# akcelerometr.net
KiCad netlist of a schematic drawn in Altium Designer
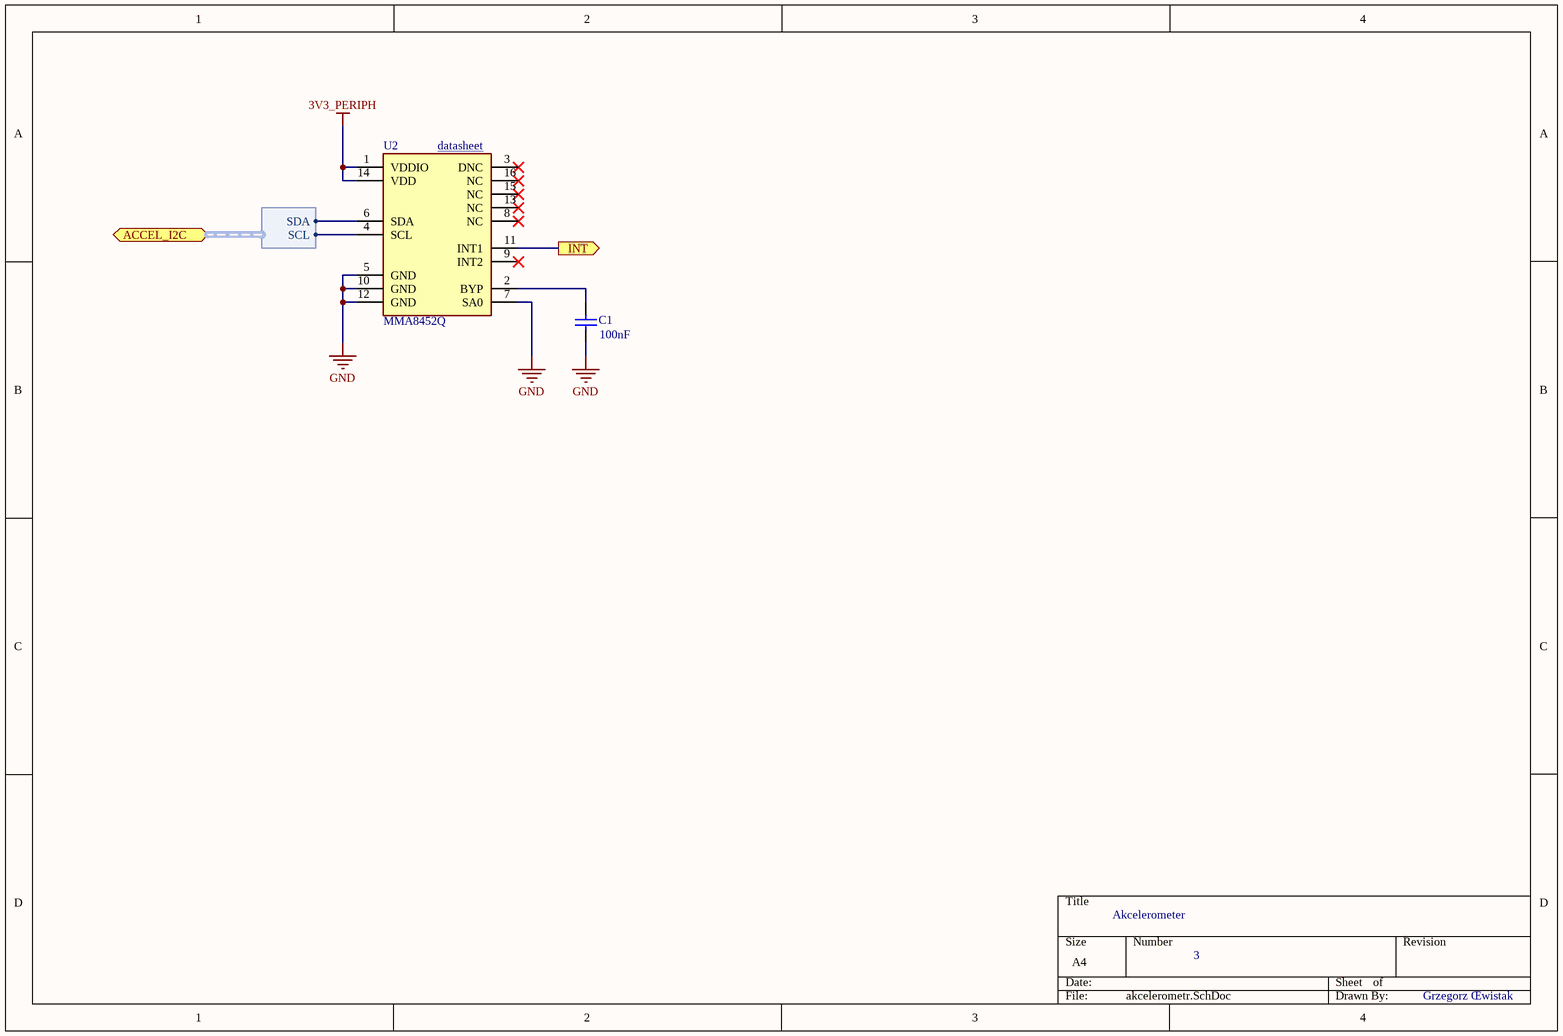
[diagram p0: akcelerometr.SchDoc]

(export (version "E")
  (design (tool "Eeschema 10.0.6"))
  (components
    (comp (ref "C1")
      (value "100nF")
      (footprint "C0805")
      (description "Capacitor")
      (fields (field (name "Comment") "Cap") (field (name "PUBLISHER") "Altium Limited"))
      (libsource (lib "Miscellaneous Devices") (part "Cap"))
    )
    (comp (ref "U2")
      (value "MMA8452Q")
      (footprint "QFN-16")
      (description "Accelerometer")
      (fields
        (field (name "MANUFACTURER_PART_NUMBER") "MMA8452QR1")
        (field (name "MOUSER PART NUMBER") "841-MMA8452QR1")
      )
      (libsource (lib "lib") (part "MMA8452QR1"))
    )
  )
  (nets
    (net (code "2") (name "/INT") (class "Default")
      (node (ref "U2") (pin "11") (pinfunction "INT1_11") (pintype "passive"))
    )
    (net (code "3") (name "/SCL") (class "Default")
      (node (ref "U2") (pin "4") (pinfunction "SCL_4") (pintype "passive"))
    )
    (net (code "4") (name "/SDA") (class "Default")
      (node (ref "U2") (pin "6") (pinfunction "SDA_6") (pintype "passive"))
    )
    (net (code "6") (name "3V3_PERIPH") (class "Default")
      (node (ref "U2") (pin "1") (pinfunction "VDDIO_1") (pintype "passive"))
      (node (ref "U2") (pin "14") (pinfunction "VDD_14") (pintype "passive"))
    )
    (net (code "7") (name "GND") (class "Default")
      (node (ref "C1") (pin "1") (pinfunction "1_1") (pintype "passive"))
      (node (ref "U2") (pin "10") (pinfunction "GND_10") (pintype "passive"))
      (node (ref "U2") (pin "12") (pinfunction "GND_12") (pintype "passive"))
      (node (ref "U2") (pin "5") (pinfunction "GND_5") (pintype "passive"))
      (node (ref "U2") (pin "7") (pinfunction "SA0_7") (pintype "passive"))
    )
    (net (code "8") (name "Net-(U2-BYP)") (class "Default")
      (node (ref "C1") (pin "2") (pinfunction "2_2") (pintype "passive"))
      (node (ref "U2") (pin "2") (pinfunction "BYP_2") (pintype "passive"))
    )
    (net (code "9") (name "unconnected-(U2-DNC-Pad3)") (class "Default")
      (node (ref "U2") (pin "3") (pinfunction "DNC_3") (pintype "passive+no_connect"))
    )
    (net (code "10") (name "unconnected-(U2-INT2-Pad9)") (class "Default")
      (node (ref "U2") (pin "9") (pinfunction "INT2_9") (pintype "passive+no_connect"))
    )
    (net (code "11") (name "unconnected-(U2-NC-Pad8)") (class "Default")
      (node (ref "U2") (pin "8") (pinfunction "NC_8") (pintype "passive+no_connect"))
    )
    (net (code "12") (name "unconnected-(U2-NC-Pad13)") (class "Default")
      (node (ref "U2") (pin "13") (pinfunction "NC_13") (pintype "passive+no_connect"))
    )
    (net (code "13") (name "unconnected-(U2-NC-Pad15)") (class "Default")
      (node (ref "U2") (pin "15") (pinfunction "NC_15") (pintype "passive+no_connect"))
    )
    (net (code "14") (name "unconnected-(U2-NC-Pad16)") (class "Default")
      (node (ref "U2") (pin "16") (pinfunction "NC_16") (pintype "passive+no_connect"))
    )
  )
)
